# PN-Power.net
KiCad netlist of a schematic drawn in Altium Designer
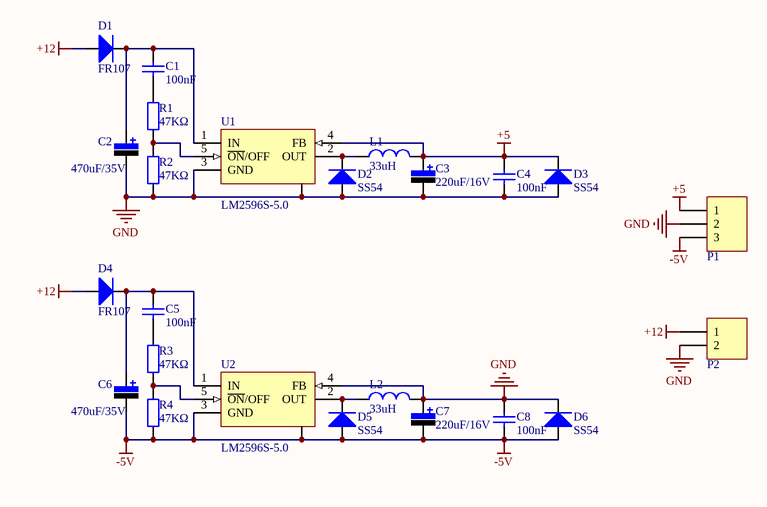
[diagram p0: PN-Power.SchDoc]

(export (version "E")
  (design (tool "Eeschema 10.0.6"))
  (components
    (comp (ref "C1")
      (value "100nF")
      (footprint "0805_C")
      (description "贴片电容")
      (libsource (lib "Miscellaneous Devices LC") (part "0805 100nF(104) 10% 50V"))
    )
    (comp (ref "C2")
      (value "470uF/35V")
      (footprint "C-RB-S10")
      (description "极性电解电容")
      (fields (field (name "PUBLISHER") "Altium Limited"))
      (libsource (lib "fszhang") (part "Cap Pol"))
    )
    (comp (ref "C3")
      (value "220uF/16V")
      (footprint "C-RB-S6")
      (description "极性电解电容")
      (fields (field (name "PUBLISHER") "Altium Limited"))
      (libsource (lib "fszhang") (part "Cap Pol"))
    )
    (comp (ref "C4")
      (value "100nF")
      (footprint "0805_C")
      (description "贴片电容")
      (libsource (lib "Miscellaneous Devices LC") (part "0805 100nF(104) 10% 50V"))
    )
    (comp (ref "C5")
      (value "100nF")
      (footprint "0805_C")
      (description "贴片电容")
      (libsource (lib "Miscellaneous Devices LC") (part "0805 100nF(104) 10% 50V"))
    )
    (comp (ref "C6")
      (value "470uF/35V")
      (footprint "C-RB-S10")
      (description "极性电解电容")
      (fields (field (name "PUBLISHER") "Altium Limited"))
      (libsource (lib "fszhang") (part "Cap Pol"))
    )
    (comp (ref "C7")
      (value "220uF/16V")
      (footprint "C-RB-S6")
      (description "极性电解电容")
      (fields (field (name "PUBLISHER") "Altium Limited"))
      (libsource (lib "fszhang") (part "Cap Pol"))
    )
    (comp (ref "C8")
      (value "100nF")
      (footprint "0805_C")
      (description "贴片电容")
      (libsource (lib "Miscellaneous Devices LC") (part "0805 100nF(104) 10% 50V"))
    )
    (comp (ref "D1")
      (value "FR107")
      (footprint "DIODE-SMA")
      (description "二极管")
      (fields (field (name "PUBLISHER") "Altium Limited"))
      (libsource (lib "fszhang") (part "Diode"))
    )
    (comp (ref "D2")
      (value "SS54")
      (footprint "DIODE-SMA")
      (description "二极管")
      (fields (field (name "PUBLISHER") "Altium Limited"))
      (libsource (lib "fszhang") (part "Diode"))
    )
    (comp (ref "D3")
      (value "SS54")
      (footprint "DIODE-SMA")
      (description "二极管")
      (fields (field (name "PUBLISHER") "Altium Limited"))
      (libsource (lib "fszhang") (part "Diode"))
    )
    (comp (ref "D4")
      (value "FR107")
      (footprint "DIODE-SMA")
      (description "二极管")
      (fields (field (name "PUBLISHER") "Altium Limited"))
      (libsource (lib "fszhang") (part "Diode"))
    )
    (comp (ref "D5")
      (value "SS54")
      (footprint "DIODE-SMA")
      (description "二极管")
      (fields (field (name "PUBLISHER") "Altium Limited"))
      (libsource (lib "fszhang") (part "Diode"))
    )
    (comp (ref "D6")
      (value "SS54")
      (footprint "DIODE-SMA")
      (description "二极管")
      (fields (field (name "PUBLISHER") "Altium Limited"))
      (libsource (lib "fszhang") (part "Diode"))
    )
    (comp (ref "L1")
      (value "33uH")
      (footprint "L-SMD-12")
      (description "电感")
      (fields (field (name "PUBLISHER") "Altium Limited"))
      (libsource (lib "fszhang") (part "Inductor"))
    )
    (comp (ref "L2")
      (value "33uH")
      (footprint "L-SMD-12")
      (description "电感")
      (fields (field (name "PUBLISHER") "Altium Limited"))
      (libsource (lib "fszhang") (part "Inductor"))
    )
    (comp (ref "P1")
      (value "Header 3")
      (footprint "HDR3X1_A")
      (description "接插件")
      (fields (field (name "PUBLISHER") "Altium Limited"))
      (libsource (lib "fszhang") (part "Header 3"))
    )
    (comp (ref "P2")
      (value "Header 2")
      (footprint "HDR2X1_A")
      (description "接插件")
      (fields (field (name "PUBLISHER") "Altium Limited"))
      (libsource (lib "fszhang") (part "Header 2"))
    )
    (comp (ref "R1")
      (value "47KΩ")
      (footprint "0805_R")
      (description "贴片电阻")
      (libsource (lib "Miscellaneous Devices LC") (part "0805 47KΩ (4702) 1%"))
    )
    (comp (ref "R2")
      (value "47KΩ")
      (footprint "0805_R")
      (description "贴片电阻")
      (libsource (lib "Miscellaneous Devices LC") (part "0805 47KΩ (4702) 1%"))
    )
    (comp (ref "R3")
      (value "47KΩ")
      (footprint "0805_R")
      (description "贴片电阻")
      (libsource (lib "Miscellaneous Devices LC") (part "0805 47KΩ (4702) 1%"))
    )
    (comp (ref "R4")
      (value "47KΩ")
      (footprint "0805_R")
      (description "贴片电阻")
      (libsource (lib "Miscellaneous Devices LC") (part "0805 47KΩ (4702) 1%"))
    )
    (comp (ref "U1")
      (value "LM2596S-5.0")
      (footprint "TO-263-5")
      (description "5V稳压芯片")
      (fields (field (name "PUBLISHER") "Altium Limited"))
      (libsource (lib "fszhang") (part "LM2596S-5.0"))
    )
    (comp (ref "U2")
      (value "LM2596S-5.0")
      (footprint "TO-263-5")
      (description "5V稳压芯片")
      (fields (field (name "PUBLISHER") "Altium Limited"))
      (libsource (lib "fszhang") (part "LM2596S-5.0"))
    )
  )
  (nets
    (net (code "1") (name "+5") (class "Default")
      (node (ref "C3") (pin "1") (pinfunction "1_1") (pintype "passive"))
      (node (ref "C4") (pin "2") (pinfunction "2_2") (pintype "passive"))
      (node (ref "D3") (pin "2") (pinfunction "K_2") (pintype "passive"))
      (node (ref "L1") (pin "2") (pinfunction "2_2") (pintype "passive"))
      (node (ref "P1") (pin "1") (pinfunction "1_1") (pintype "passive"))
      (node (ref "U1") (pin "4") (pinfunction "FB_4") (pintype "input"))
    )
    (net (code "2") (name "+12") (class "Default")
      (node (ref "D1") (pin "1") (pinfunction "A_1") (pintype "passive"))
      (node (ref "D4") (pin "1") (pinfunction "A_1") (pintype "passive"))
      (node (ref "P2") (pin "1") (pinfunction "1_1") (pintype "passive"))
    )
    (net (code "3") (name "-5V") (class "Default")
      (node (ref "C6") (pin "2") (pinfunction "2_2") (pintype "passive"))
      (node (ref "C7") (pin "2") (pinfunction "2_2") (pintype "passive"))
      (node (ref "C8") (pin "1") (pinfunction "1_1") (pintype "passive"))
      (node (ref "D5") (pin "1") (pinfunction "A_1") (pintype "passive"))
      (node (ref "D6") (pin "1") (pinfunction "A_1") (pintype "passive"))
      (node (ref "P1") (pin "3") (pinfunction "3_3") (pintype "passive"))
      (node (ref "R4") (pin "1") (pinfunction "1_1") (pintype "passive"))
      (node (ref "U2") (pin "3") (pinfunction "GND_3") (pintype "power_in"))
      (node (ref "U2") (pin "6") (pinfunction "6_6") (pintype "power_in"))
    )
    (net (code "4") (name "GND") (class "Default")
      (node (ref "C2") (pin "2") (pinfunction "2_2") (pintype "passive"))
      (node (ref "C3") (pin "2") (pinfunction "2_2") (pintype "passive"))
      (node (ref "C4") (pin "1") (pinfunction "1_1") (pintype "passive"))
      (node (ref "C7") (pin "1") (pinfunction "1_1") (pintype "passive"))
      (node (ref "C8") (pin "2") (pinfunction "2_2") (pintype "passive"))
      (node (ref "D2") (pin "1") (pinfunction "A_1") (pintype "passive"))
      (node (ref "D3") (pin "1") (pinfunction "A_1") (pintype "passive"))
      (node (ref "D6") (pin "2") (pinfunction "K_2") (pintype "passive"))
      (node (ref "L2") (pin "2") (pinfunction "2_2") (pintype "passive"))
      (node (ref "P1") (pin "2") (pinfunction "2_2") (pintype "passive"))
      (node (ref "P2") (pin "2") (pinfunction "2_2") (pintype "passive"))
      (node (ref "R2") (pin "1") (pinfunction "1_1") (pintype "passive"))
      (node (ref "U1") (pin "3") (pinfunction "GND_3") (pintype "power_in"))
      (node (ref "U1") (pin "6") (pinfunction "6_6") (pintype "power_in"))
      (node (ref "U2") (pin "4") (pinfunction "FB_4") (pintype "input"))
    )
    (net (code "5") (name "Net-(C1-Pad1)") (class "Default")
      (node (ref "C1") (pin "1") (pinfunction "1_1") (pintype "passive"))
      (node (ref "R1") (pin "2") (pinfunction "2_2") (pintype "passive"))
    )
    (net (code "6") (name "Net-(C5-Pad1)") (class "Default")
      (node (ref "C5") (pin "1") (pinfunction "1_1") (pintype "passive"))
      (node (ref "R3") (pin "2") (pinfunction "2_2") (pintype "passive"))
    )
    (net (code "7") (name "Net-(D1-K)") (class "Default")
      (node (ref "C1") (pin "2") (pinfunction "2_2") (pintype "passive"))
      (node (ref "C2") (pin "1") (pinfunction "1_1") (pintype "passive"))
      (node (ref "D1") (pin "2") (pinfunction "K_2") (pintype "passive"))
      (node (ref "U1") (pin "1") (pinfunction "IN_1") (pintype "power_in"))
    )
    (net (code "8") (name "Net-(D2-K)") (class "Default")
      (node (ref "D2") (pin "2") (pinfunction "K_2") (pintype "passive"))
      (node (ref "L1") (pin "1") (pinfunction "1_1") (pintype "passive"))
      (node (ref "U1") (pin "2") (pinfunction "OUT_2") (pintype "power_in"))
    )
    (net (code "9") (name "Net-(D4-K)") (class "Default")
      (node (ref "C5") (pin "2") (pinfunction "2_2") (pintype "passive"))
      (node (ref "C6") (pin "1") (pinfunction "1_1") (pintype "passive"))
      (node (ref "D4") (pin "2") (pinfunction "K_2") (pintype "passive"))
      (node (ref "U2") (pin "1") (pinfunction "IN_1") (pintype "power_in"))
    )
    (net (code "10") (name "Net-(D5-K)") (class "Default")
      (node (ref "D5") (pin "2") (pinfunction "K_2") (pintype "passive"))
      (node (ref "L2") (pin "1") (pinfunction "1_1") (pintype "passive"))
      (node (ref "U2") (pin "2") (pinfunction "OUT_2") (pintype "power_in"))
    )
    (net (code "11") (name "Net-(U1-~{ON}{slash}OFF)") (class "Default")
      (node (ref "R1") (pin "1") (pinfunction "1_1") (pintype "passive"))
      (node (ref "R2") (pin "2") (pinfunction "2_2") (pintype "passive"))
      (node (ref "U1") (pin "5") (pinfunction "~{ON}/OFF_5") (pintype "input"))
    )
    (net (code "12") (name "Net-(U2-~{ON}{slash}OFF)") (class "Default")
      (node (ref "R3") (pin "1") (pinfunction "1_1") (pintype "passive"))
      (node (ref "R4") (pin "2") (pinfunction "2_2") (pintype "passive"))
      (node (ref "U2") (pin "5") (pinfunction "~{ON}/OFF_5") (pintype "input"))
    )
  )
)
